# Sheet3.net
KiCad netlist of a schematic drawn in Altium Designer
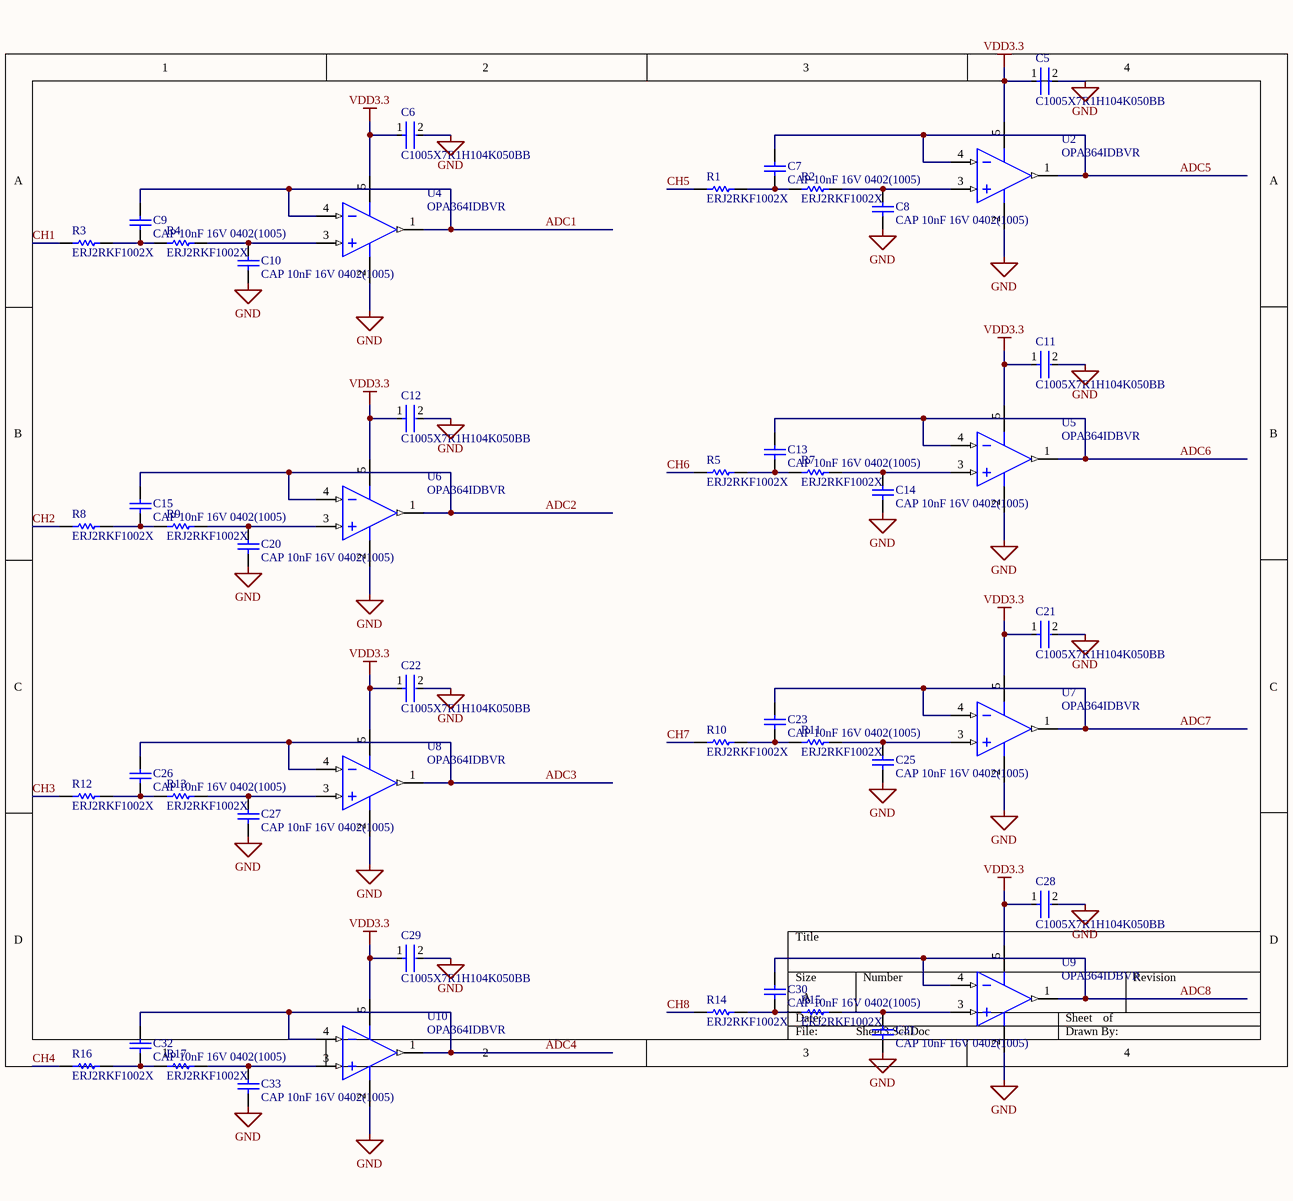
[diagram p0: Sheet3.SchDoc]

(export (version "E")
  (design (tool "Eeschema 10.0.6"))
  (components
    (comp (ref "C5")
      (value "C1005X7R1H104K050BB")
      (footprint "FP-C1005-050-0_05-IPC_C")
      (description "Multilayer Ceramic Capacitors 100nF ±10% 50V X7R SMD 0402")
      (fields (field (name "VOLTAGE") "50V") (field (name "TOLERANCE") "10%"))
      (libsource (lib "Altium Content Vault") (part "b4654b650e69147ec39a6b967a45e02"))
    )
    (comp (ref "C6")
      (value "C1005X7R1H104K050BB")
      (footprint "FP-C1005-050-0_05-IPC_C")
      (description "Multilayer Ceramic Capacitors 100nF ±10% 50V X7R SMD 0402")
      (fields (field (name "VOLTAGE") "50V") (field (name "TOLERANCE") "10%"))
      (libsource (lib "Altium Content Vault") (part "b4654b650e69147ec39a6b967a45e02"))
    )
    (comp (ref "C7")
      (value "CAP 10nF 16V 0402(1005)")
      (footprint "CAPC0402(1005)60_M")
      (description "CAP 10nF 16V -20% to +80% 0402 (1005 Metric) Thickness 0.6mm SMD")
      (fields (field (name "TOLERANCE") "-20% to +80%"))
      (libsource (lib "Altium Content Vault") (part "CAP"))
    )
    (comp (ref "C8")
      (value "CAP 10nF 16V 0402(1005)")
      (footprint "CAPC0402(1005)60_M")
      (description "CAP 10nF 16V -20% to +80% 0402 (1005 Metric) Thickness 0.6mm SMD")
      (fields (field (name "TOLERANCE") "-20% to +80%"))
      (libsource (lib "Altium Content Vault") (part "CAP"))
    )
    (comp (ref "C9")
      (value "CAP 10nF 16V 0402(1005)")
      (footprint "CAPC0402(1005)60_M")
      (description "CAP 10nF 16V -20% to +80% 0402 (1005 Metric) Thickness 0.6mm SMD")
      (fields (field (name "TOLERANCE") "-20% to +80%"))
      (libsource (lib "Altium Content Vault") (part "CAP"))
    )
    (comp (ref "C10")
      (value "CAP 10nF 16V 0402(1005)")
      (footprint "CAPC0402(1005)60_M")
      (description "CAP 10nF 16V -20% to +80% 0402 (1005 Metric) Thickness 0.6mm SMD")
      (fields (field (name "TOLERANCE") "-20% to +80%"))
      (libsource (lib "Altium Content Vault") (part "CAP"))
    )
    (comp (ref "C11")
      (value "C1005X7R1H104K050BB")
      (footprint "FP-C1005-050-0_05-IPC_C")
      (description "Multilayer Ceramic Capacitors 100nF ±10% 50V X7R SMD 0402")
      (fields (field (name "VOLTAGE") "50V") (field (name "TOLERANCE") "10%"))
      (libsource (lib "Altium Content Vault") (part "b4654b650e69147ec39a6b967a45e02"))
    )
    (comp (ref "C12")
      (value "C1005X7R1H104K050BB")
      (footprint "FP-C1005-050-0_05-IPC_C")
      (description "Multilayer Ceramic Capacitors 100nF ±10% 50V X7R SMD 0402")
      (fields (field (name "VOLTAGE") "50V") (field (name "TOLERANCE") "10%"))
      (libsource (lib "Altium Content Vault") (part "b4654b650e69147ec39a6b967a45e02"))
    )
    (comp (ref "C13")
      (value "CAP 10nF 16V 0402(1005)")
      (footprint "CAPC0402(1005)60_M")
      (description "CAP 10nF 16V -20% to +80% 0402 (1005 Metric) Thickness 0.6mm SMD")
      (fields (field (name "TOLERANCE") "-20% to +80%"))
      (libsource (lib "Altium Content Vault") (part "CAP"))
    )
    (comp (ref "C14")
      (value "CAP 10nF 16V 0402(1005)")
      (footprint "CAPC0402(1005)60_M")
      (description "CAP 10nF 16V -20% to +80% 0402 (1005 Metric) Thickness 0.6mm SMD")
      (fields (field (name "TOLERANCE") "-20% to +80%"))
      (libsource (lib "Altium Content Vault") (part "CAP"))
    )
    (comp (ref "C15")
      (value "CAP 10nF 16V 0402(1005)")
      (footprint "CAPC0402(1005)60_M")
      (description "CAP 10nF 16V -20% to +80% 0402 (1005 Metric) Thickness 0.6mm SMD")
      (fields (field (name "TOLERANCE") "-20% to +80%"))
      (libsource (lib "Altium Content Vault") (part "CAP"))
    )
    (comp (ref "C20")
      (value "CAP 10nF 16V 0402(1005)")
      (footprint "CAPC0402(1005)60_M")
      (description "CAP 10nF 16V -20% to +80% 0402 (1005 Metric) Thickness 0.6mm SMD")
      (fields (field (name "TOLERANCE") "-20% to +80%"))
      (libsource (lib "Altium Content Vault") (part "CAP"))
    )
    (comp (ref "C21")
      (value "C1005X7R1H104K050BB")
      (footprint "FP-C1005-050-0_05-IPC_C")
      (description "Multilayer Ceramic Capacitors 100nF ±10% 50V X7R SMD 0402")
      (fields (field (name "VOLTAGE") "50V") (field (name "TOLERANCE") "10%"))
      (libsource (lib "Altium Content Vault") (part "b4654b650e69147ec39a6b967a45e02"))
    )
    (comp (ref "C22")
      (value "C1005X7R1H104K050BB")
      (footprint "FP-C1005-050-0_05-IPC_C")
      (description "Multilayer Ceramic Capacitors 100nF ±10% 50V X7R SMD 0402")
      (fields (field (name "VOLTAGE") "50V") (field (name "TOLERANCE") "10%"))
      (libsource (lib "Altium Content Vault") (part "b4654b650e69147ec39a6b967a45e02"))
    )
    (comp (ref "C23")
      (value "CAP 10nF 16V 0402(1005)")
      (footprint "CAPC0402(1005)60_M")
      (description "CAP 10nF 16V -20% to +80% 0402 (1005 Metric) Thickness 0.6mm SMD")
      (fields (field (name "TOLERANCE") "-20% to +80%"))
      (libsource (lib "Altium Content Vault") (part "CAP"))
    )
    (comp (ref "C25")
      (value "CAP 10nF 16V 0402(1005)")
      (footprint "CAPC0402(1005)60_M")
      (description "CAP 10nF 16V -20% to +80% 0402 (1005 Metric) Thickness 0.6mm SMD")
      (fields (field (name "TOLERANCE") "-20% to +80%"))
      (libsource (lib "Altium Content Vault") (part "CAP"))
    )
    (comp (ref "C26")
      (value "CAP 10nF 16V 0402(1005)")
      (footprint "CAPC0402(1005)60_M")
      (description "CAP 10nF 16V -20% to +80% 0402 (1005 Metric) Thickness 0.6mm SMD")
      (fields (field (name "TOLERANCE") "-20% to +80%"))
      (libsource (lib "Altium Content Vault") (part "CAP"))
    )
    (comp (ref "C27")
      (value "CAP 10nF 16V 0402(1005)")
      (footprint "CAPC0402(1005)60_M")
      (description "CAP 10nF 16V -20% to +80% 0402 (1005 Metric) Thickness 0.6mm SMD")
      (fields (field (name "TOLERANCE") "-20% to +80%"))
      (libsource (lib "Altium Content Vault") (part "CAP"))
    )
    (comp (ref "C28")
      (value "C1005X7R1H104K050BB")
      (footprint "FP-C1005-050-0_05-IPC_C")
      (description "Multilayer Ceramic Capacitors 100nF ±10% 50V X7R SMD 0402")
      (fields (field (name "VOLTAGE") "50V") (field (name "TOLERANCE") "10%"))
      (libsource (lib "Altium Content Vault") (part "b4654b650e69147ec39a6b967a45e02"))
    )
    (comp (ref "C29")
      (value "C1005X7R1H104K050BB")
      (footprint "FP-C1005-050-0_05-IPC_C")
      (description "Multilayer Ceramic Capacitors 100nF ±10% 50V X7R SMD 0402")
      (fields (field (name "VOLTAGE") "50V") (field (name "TOLERANCE") "10%"))
      (libsource (lib "Altium Content Vault") (part "b4654b650e69147ec39a6b967a45e02"))
    )
    (comp (ref "C30")
      (value "CAP 10nF 16V 0402(1005)")
      (footprint "CAPC0402(1005)60_M")
      (description "CAP 10nF 16V -20% to +80% 0402 (1005 Metric) Thickness 0.6mm SMD")
      (fields (field (name "TOLERANCE") "-20% to +80%"))
      (libsource (lib "Altium Content Vault") (part "CAP"))
    )
    (comp (ref "C31")
      (value "CAP 10nF 16V 0402(1005)")
      (footprint "CAPC0402(1005)60_M")
      (description "CAP 10nF 16V -20% to +80% 0402 (1005 Metric) Thickness 0.6mm SMD")
      (fields (field (name "TOLERANCE") "-20% to +80%"))
      (libsource (lib "Altium Content Vault") (part "CAP"))
    )
    (comp (ref "C32")
      (value "CAP 10nF 16V 0402(1005)")
      (footprint "CAPC0402(1005)60_M")
      (description "CAP 10nF 16V -20% to +80% 0402 (1005 Metric) Thickness 0.6mm SMD")
      (fields (field (name "TOLERANCE") "-20% to +80%"))
      (libsource (lib "Altium Content Vault") (part "CAP"))
    )
    (comp (ref "C33")
      (value "CAP 10nF 16V 0402(1005)")
      (footprint "CAPC0402(1005)60_M")
      (description "CAP 10nF 16V -20% to +80% 0402 (1005 Metric) Thickness 0.6mm SMD")
      (fields (field (name "TOLERANCE") "-20% to +80%"))
      (libsource (lib "Altium Content Vault") (part "CAP"))
    )
    (comp (ref "R1")
      (value "ERJ2RKF1002X")
      (footprint "RESC1005X40X25LL05T05")
      (description "Chip Resistor, 10 KOhm, +/- 1%, 0.1 W, -55 to 155 degC, 0402 (1005 Metric), RoHS, Tape and Reel")
      (fields (field (name "TOLERANCE") "1%") (field (name "MANUFACTURER") "Panasonic"))
      (libsource (lib "Altium Content Vault") (part "RES-2"))
    )
    (comp (ref "R2")
      (value "ERJ2RKF1002X")
      (footprint "RESC1005X40X25LL05T05")
      (description "Chip Resistor, 10 KOhm, +/- 1%, 0.1 W, -55 to 155 degC, 0402 (1005 Metric), RoHS, Tape and Reel")
      (fields (field (name "TOLERANCE") "1%") (field (name "MANUFACTURER") "Panasonic"))
      (libsource (lib "Altium Content Vault") (part "RES-2"))
    )
    (comp (ref "R3")
      (value "ERJ2RKF1002X")
      (footprint "RESC1005X40X25LL05T05")
      (description "Chip Resistor, 10 KOhm, +/- 1%, 0.1 W, -55 to 155 degC, 0402 (1005 Metric), RoHS, Tape and Reel")
      (fields (field (name "TOLERANCE") "1%") (field (name "MANUFACTURER") "Panasonic"))
      (libsource (lib "Altium Content Vault") (part "RES-2"))
    )
    (comp (ref "R4")
      (value "ERJ2RKF1002X")
      (footprint "RESC1005X40X25LL05T05")
      (description "Chip Resistor, 10 KOhm, +/- 1%, 0.1 W, -55 to 155 degC, 0402 (1005 Metric), RoHS, Tape and Reel")
      (fields (field (name "TOLERANCE") "1%") (field (name "MANUFACTURER") "Panasonic"))
      (libsource (lib "Altium Content Vault") (part "RES-2"))
    )
    (comp (ref "R5")
      (value "ERJ2RKF1002X")
      (footprint "RESC1005X40X25LL05T05")
      (description "Chip Resistor, 10 KOhm, +/- 1%, 0.1 W, -55 to 155 degC, 0402 (1005 Metric), RoHS, Tape and Reel")
      (fields (field (name "TOLERANCE") "1%") (field (name "MANUFACTURER") "Panasonic"))
      (libsource (lib "Altium Content Vault") (part "RES-2"))
    )
    (comp (ref "R7")
      (value "ERJ2RKF1002X")
      (footprint "RESC1005X40X25LL05T05")
      (description "Chip Resistor, 10 KOhm, +/- 1%, 0.1 W, -55 to 155 degC, 0402 (1005 Metric), RoHS, Tape and Reel")
      (fields (field (name "TOLERANCE") "1%") (field (name "MANUFACTURER") "Panasonic"))
      (libsource (lib "Altium Content Vault") (part "RES-2"))
    )
    (comp (ref "R8")
      (value "ERJ2RKF1002X")
      (footprint "RESC1005X40X25LL05T05")
      (description "Chip Resistor, 10 KOhm, +/- 1%, 0.1 W, -55 to 155 degC, 0402 (1005 Metric), RoHS, Tape and Reel")
      (fields (field (name "TOLERANCE") "1%") (field (name "MANUFACTURER") "Panasonic"))
      (libsource (lib "Altium Content Vault") (part "RES-2"))
    )
    (comp (ref "R9")
      (value "ERJ2RKF1002X")
      (footprint "RESC1005X40X25LL05T05")
      (description "Chip Resistor, 10 KOhm, +/- 1%, 0.1 W, -55 to 155 degC, 0402 (1005 Metric), RoHS, Tape and Reel")
      (fields (field (name "TOLERANCE") "1%") (field (name "MANUFACTURER") "Panasonic"))
      (libsource (lib "Altium Content Vault") (part "RES-2"))
    )
    (comp (ref "R10")
      (value "ERJ2RKF1002X")
      (footprint "RESC1005X40X25LL05T05")
      (description "Chip Resistor, 10 KOhm, +/- 1%, 0.1 W, -55 to 155 degC, 0402 (1005 Metric), RoHS, Tape and Reel")
      (fields (field (name "TOLERANCE") "1%") (field (name "MANUFACTURER") "Panasonic"))
      (libsource (lib "Altium Content Vault") (part "RES-2"))
    )
    (comp (ref "R11")
      (value "ERJ2RKF1002X")
      (footprint "RESC1005X40X25LL05T05")
      (description "Chip Resistor, 10 KOhm, +/- 1%, 0.1 W, -55 to 155 degC, 0402 (1005 Metric), RoHS, Tape and Reel")
      (fields (field (name "TOLERANCE") "1%") (field (name "MANUFACTURER") "Panasonic"))
      (libsource (lib "Altium Content Vault") (part "RES-2"))
    )
    (comp (ref "R12")
      (value "ERJ2RKF1002X")
      (footprint "RESC1005X40X25LL05T05")
      (description "Chip Resistor, 10 KOhm, +/- 1%, 0.1 W, -55 to 155 degC, 0402 (1005 Metric), RoHS, Tape and Reel")
      (fields (field (name "TOLERANCE") "1%") (field (name "MANUFACTURER") "Panasonic"))
      (libsource (lib "Altium Content Vault") (part "RES-2"))
    )
    (comp (ref "R13")
      (value "ERJ2RKF1002X")
      (footprint "RESC1005X40X25LL05T05")
      (description "Chip Resistor, 10 KOhm, +/- 1%, 0.1 W, -55 to 155 degC, 0402 (1005 Metric), RoHS, Tape and Reel")
      (fields (field (name "TOLERANCE") "1%") (field (name "MANUFACTURER") "Panasonic"))
      (libsource (lib "Altium Content Vault") (part "RES-2"))
    )
    (comp (ref "R14")
      (value "ERJ2RKF1002X")
      (footprint "RESC1005X40X25LL05T05")
      (description "Chip Resistor, 10 KOhm, +/- 1%, 0.1 W, -55 to 155 degC, 0402 (1005 Metric), RoHS, Tape and Reel")
      (fields (field (name "TOLERANCE") "1%") (field (name "MANUFACTURER") "Panasonic"))
      (libsource (lib "Altium Content Vault") (part "RES-2"))
    )
    (comp (ref "R15")
      (value "ERJ2RKF1002X")
      (footprint "RESC1005X40X25LL05T05")
      (description "Chip Resistor, 10 KOhm, +/- 1%, 0.1 W, -55 to 155 degC, 0402 (1005 Metric), RoHS, Tape and Reel")
      (fields (field (name "TOLERANCE") "1%") (field (name "MANUFACTURER") "Panasonic"))
      (libsource (lib "Altium Content Vault") (part "RES-2"))
    )
    (comp (ref "R16")
      (value "ERJ2RKF1002X")
      (footprint "RESC1005X40X25LL05T05")
      (description "Chip Resistor, 10 KOhm, +/- 1%, 0.1 W, -55 to 155 degC, 0402 (1005 Metric), RoHS, Tape and Reel")
      (fields (field (name "TOLERANCE") "1%") (field (name "MANUFACTURER") "Panasonic"))
      (libsource (lib "Altium Content Vault") (part "RES-2"))
    )
    (comp (ref "R17")
      (value "ERJ2RKF1002X")
      (footprint "RESC1005X40X25LL05T05")
      (description "Chip Resistor, 10 KOhm, +/- 1%, 0.1 W, -55 to 155 degC, 0402 (1005 Metric), RoHS, Tape and Reel")
      (fields (field (name "TOLERANCE") "1%") (field (name "MANUFACTURER") "Panasonic"))
      (libsource (lib "Altium Content Vault") (part "RES-2"))
    )
    (comp (ref "U2")
      (value "OPA364IDBVR")
      (footprint "DBV0005A_M")
      (fields (field (name "MANUFACTURER") "Texas Instruments"))
      (libsource (lib "Altium Content Vault") (part "TI-OPA364_5DBV5"))
    )
    (comp (ref "U4")
      (value "OPA364IDBVR")
      (footprint "DBV0005A_M")
      (fields (field (name "MANUFACTURER") "Texas Instruments"))
      (libsource (lib "Altium Content Vault") (part "TI-OPA364_5DBV5"))
    )
    (comp (ref "U5")
      (value "OPA364IDBVR")
      (footprint "DBV0005A_M")
      (fields (field (name "MANUFACTURER") "Texas Instruments"))
      (libsource (lib "Altium Content Vault") (part "TI-OPA364_5DBV5"))
    )
    (comp (ref "U6")
      (value "OPA364IDBVR")
      (footprint "DBV0005A_M")
      (fields (field (name "MANUFACTURER") "Texas Instruments"))
      (libsource (lib "Altium Content Vault") (part "TI-OPA364_5DBV5"))
    )
    (comp (ref "U7")
      (value "OPA364IDBVR")
      (footprint "DBV0005A_M")
      (fields (field (name "MANUFACTURER") "Texas Instruments"))
      (libsource (lib "Altium Content Vault") (part "TI-OPA364_5DBV5"))
    )
    (comp (ref "U8")
      (value "OPA364IDBVR")
      (footprint "DBV0005A_M")
      (fields (field (name "MANUFACTURER") "Texas Instruments"))
      (libsource (lib "Altium Content Vault") (part "TI-OPA364_5DBV5"))
    )
    (comp (ref "U9")
      (value "OPA364IDBVR")
      (footprint "DBV0005A_M")
      (fields (field (name "MANUFACTURER") "Texas Instruments"))
      (libsource (lib "Altium Content Vault") (part "TI-OPA364_5DBV5"))
    )
    (comp (ref "U10")
      (value "OPA364IDBVR")
      (footprint "DBV0005A_M")
      (fields (field (name "MANUFACTURER") "Texas Instruments"))
      (libsource (lib "Altium Content Vault") (part "TI-OPA364_5DBV5"))
    )
  )
  (nets
    (net (code "1") (name "/ADC1") (class "Default")
      (node (ref "C9") (pin "2") (pinfunction "2_2") (pintype "passive"))
      (node (ref "U4") (pin "1") (pinfunction "VOUT_1") (pintype "output"))
      (node (ref "U4") (pin "4") (pinfunction "IN-_4") (pintype "input"))
    )
    (net (code "2") (name "/ADC2") (class "Default")
      (node (ref "C15") (pin "2") (pinfunction "2_2") (pintype "passive"))
      (node (ref "U6") (pin "1") (pinfunction "VOUT_1") (pintype "output"))
      (node (ref "U6") (pin "4") (pinfunction "IN-_4") (pintype "input"))
    )
    (net (code "3") (name "/ADC3") (class "Default")
      (node (ref "C26") (pin "2") (pinfunction "2_2") (pintype "passive"))
      (node (ref "U8") (pin "1") (pinfunction "VOUT_1") (pintype "output"))
      (node (ref "U8") (pin "4") (pinfunction "IN-_4") (pintype "input"))
    )
    (net (code "4") (name "/ADC4") (class "Default")
      (node (ref "C32") (pin "2") (pinfunction "2_2") (pintype "passive"))
      (node (ref "U10") (pin "1") (pinfunction "VOUT_1") (pintype "output"))
      (node (ref "U10") (pin "4") (pinfunction "IN-_4") (pintype "input"))
    )
    (net (code "5") (name "/ADC5") (class "Default")
      (node (ref "C7") (pin "2") (pinfunction "2_2") (pintype "passive"))
      (node (ref "U2") (pin "1") (pinfunction "VOUT_1") (pintype "output"))
      (node (ref "U2") (pin "4") (pinfunction "IN-_4") (pintype "input"))
    )
    (net (code "6") (name "/ADC6") (class "Default")
      (node (ref "C13") (pin "2") (pinfunction "2_2") (pintype "passive"))
      (node (ref "U5") (pin "1") (pinfunction "VOUT_1") (pintype "output"))
      (node (ref "U5") (pin "4") (pinfunction "IN-_4") (pintype "input"))
    )
    (net (code "7") (name "/ADC7") (class "Default")
      (node (ref "C23") (pin "2") (pinfunction "2_2") (pintype "passive"))
      (node (ref "U7") (pin "1") (pinfunction "VOUT_1") (pintype "output"))
      (node (ref "U7") (pin "4") (pinfunction "IN-_4") (pintype "input"))
    )
    (net (code "8") (name "/ADC8") (class "Default")
      (node (ref "C30") (pin "2") (pinfunction "2_2") (pintype "passive"))
      (node (ref "U9") (pin "1") (pinfunction "VOUT_1") (pintype "output"))
      (node (ref "U9") (pin "4") (pinfunction "IN-_4") (pintype "input"))
    )
    (net (code "9") (name "/CH1") (class "Default")
      (node (ref "R3") (pin "1") (pinfunction "1_1") (pintype "passive"))
    )
    (net (code "10") (name "/CH2") (class "Default")
      (node (ref "R8") (pin "1") (pinfunction "1_1") (pintype "passive"))
    )
    (net (code "11") (name "/CH3") (class "Default")
      (node (ref "R12") (pin "1") (pinfunction "1_1") (pintype "passive"))
    )
    (net (code "12") (name "/CH4") (class "Default")
      (node (ref "R16") (pin "1") (pinfunction "1_1") (pintype "passive"))
    )
    (net (code "13") (name "/CH5") (class "Default")
      (node (ref "R1") (pin "1") (pinfunction "1_1") (pintype "passive"))
    )
    (net (code "14") (name "/CH6") (class "Default")
      (node (ref "R5") (pin "1") (pinfunction "1_1") (pintype "passive"))
    )
    (net (code "15") (name "/CH7") (class "Default")
      (node (ref "R10") (pin "1") (pinfunction "1_1") (pintype "passive"))
    )
    (net (code "16") (name "/CH8") (class "Default")
      (node (ref "R14") (pin "1") (pinfunction "1_1") (pintype "passive"))
    )
    (net (code "17") (name "GND") (class "Default")
      (node (ref "C10") (pin "1") (pinfunction "1_1") (pintype "passive"))
      (node (ref "C11") (pin "2") (pinfunction "2_2") (pintype "passive"))
      (node (ref "C12") (pin "2") (pinfunction "2_2") (pintype "passive"))
      (node (ref "C14") (pin "1") (pinfunction "1_1") (pintype "passive"))
      (node (ref "C20") (pin "1") (pinfunction "1_1") (pintype "passive"))
      (node (ref "C21") (pin "2") (pinfunction "2_2") (pintype "passive"))
      (node (ref "C22") (pin "2") (pinfunction "2_2") (pintype "passive"))
      (node (ref "C25") (pin "1") (pinfunction "1_1") (pintype "passive"))
      (node (ref "C27") (pin "1") (pinfunction "1_1") (pintype "passive"))
      (node (ref "C28") (pin "2") (pinfunction "2_2") (pintype "passive"))
      (node (ref "C29") (pin "2") (pinfunction "2_2") (pintype "passive"))
      (node (ref "C31") (pin "1") (pinfunction "1_1") (pintype "passive"))
      (node (ref "C33") (pin "1") (pinfunction "1_1") (pintype "passive"))
      (node (ref "C5") (pin "2") (pinfunction "2_2") (pintype "passive"))
      (node (ref "C6") (pin "2") (pinfunction "2_2") (pintype "passive"))
      (node (ref "C8") (pin "1") (pinfunction "1_1") (pintype "passive"))
      (node (ref "U10") (pin "2") (pinfunction "V-_2") (pintype "power_in"))
      (node (ref "U2") (pin "2") (pinfunction "V-_2") (pintype "power_in"))
      (node (ref "U4") (pin "2") (pinfunction "V-_2") (pintype "power_in"))
      (node (ref "U5") (pin "2") (pinfunction "V-_2") (pintype "power_in"))
      (node (ref "U6") (pin "2") (pinfunction "V-_2") (pintype "power_in"))
      (node (ref "U7") (pin "2") (pinfunction "V-_2") (pintype "power_in"))
      (node (ref "U8") (pin "2") (pinfunction "V-_2") (pintype "power_in"))
      (node (ref "U9") (pin "2") (pinfunction "V-_2") (pintype "power_in"))
    )
    (net (code "18") (name "Net-(C7-Pad1)") (class "Default")
      (node (ref "C7") (pin "1") (pinfunction "1_1") (pintype "passive"))
      (node (ref "R1") (pin "2") (pinfunction "2_2") (pintype "passive"))
      (node (ref "R2") (pin "1") (pinfunction "1_1") (pintype "passive"))
    )
    (net (code "19") (name "Net-(C9-Pad1)") (class "Default")
      (node (ref "C9") (pin "1") (pinfunction "1_1") (pintype "passive"))
      (node (ref "R3") (pin "2") (pinfunction "2_2") (pintype "passive"))
      (node (ref "R4") (pin "1") (pinfunction "1_1") (pintype "passive"))
    )
    (net (code "20") (name "Net-(C13-Pad1)") (class "Default")
      (node (ref "C13") (pin "1") (pinfunction "1_1") (pintype "passive"))
      (node (ref "R5") (pin "2") (pinfunction "2_2") (pintype "passive"))
      (node (ref "R7") (pin "1") (pinfunction "1_1") (pintype "passive"))
    )
    (net (code "21") (name "Net-(C15-Pad1)") (class "Default")
      (node (ref "C15") (pin "1") (pinfunction "1_1") (pintype "passive"))
      (node (ref "R8") (pin "2") (pinfunction "2_2") (pintype "passive"))
      (node (ref "R9") (pin "1") (pinfunction "1_1") (pintype "passive"))
    )
    (net (code "22") (name "Net-(C23-Pad1)") (class "Default")
      (node (ref "C23") (pin "1") (pinfunction "1_1") (pintype "passive"))
      (node (ref "R10") (pin "2") (pinfunction "2_2") (pintype "passive"))
      (node (ref "R11") (pin "1") (pinfunction "1_1") (pintype "passive"))
    )
    (net (code "23") (name "Net-(C26-Pad1)") (class "Default")
      (node (ref "C26") (pin "1") (pinfunction "1_1") (pintype "passive"))
      (node (ref "R12") (pin "2") (pinfunction "2_2") (pintype "passive"))
      (node (ref "R13") (pin "1") (pinfunction "1_1") (pintype "passive"))
    )
    (net (code "24") (name "Net-(C30-Pad1)") (class "Default")
      (node (ref "C30") (pin "1") (pinfunction "1_1") (pintype "passive"))
      (node (ref "R14") (pin "2") (pinfunction "2_2") (pintype "passive"))
      (node (ref "R15") (pin "1") (pinfunction "1_1") (pintype "passive"))
    )
    (net (code "25") (name "Net-(C32-Pad1)") (class "Default")
      (node (ref "C32") (pin "1") (pinfunction "1_1") (pintype "passive"))
      (node (ref "R16") (pin "2") (pinfunction "2_2") (pintype "passive"))
      (node (ref "R17") (pin "1") (pinfunction "1_1") (pintype "passive"))
    )
    (net (code "26") (name "Net-(U2-IN+)") (class "Default")
      (node (ref "C8") (pin "2") (pinfunction "2_2") (pintype "passive"))
      (node (ref "R2") (pin "2") (pinfunction "2_2") (pintype "passive"))
      (node (ref "U2") (pin "3") (pinfunction "IN+_3") (pintype "input"))
    )
    (net (code "27") (name "Net-(U4-IN+)") (class "Default")
      (node (ref "C10") (pin "2") (pinfunction "2_2") (pintype "passive"))
      (node (ref "R4") (pin "2") (pinfunction "2_2") (pintype "passive"))
      (node (ref "U4") (pin "3") (pinfunction "IN+_3") (pintype "input"))
    )
    (net (code "28") (name "Net-(U5-IN+)") (class "Default")
      (node (ref "C14") (pin "2") (pinfunction "2_2") (pintype "passive"))
      (node (ref "R7") (pin "2") (pinfunction "2_2") (pintype "passive"))
      (node (ref "U5") (pin "3") (pinfunction "IN+_3") (pintype "input"))
    )
    (net (code "29") (name "Net-(U6-IN+)") (class "Default")
      (node (ref "C20") (pin "2") (pinfunction "2_2") (pintype "passive"))
      (node (ref "R9") (pin "2") (pinfunction "2_2") (pintype "passive"))
      (node (ref "U6") (pin "3") (pinfunction "IN+_3") (pintype "input"))
    )
    (net (code "30") (name "Net-(U7-IN+)") (class "Default")
      (node (ref "C25") (pin "2") (pinfunction "2_2") (pintype "passive"))
      (node (ref "R11") (pin "2") (pinfunction "2_2") (pintype "passive"))
      (node (ref "U7") (pin "3") (pinfunction "IN+_3") (pintype "input"))
    )
    (net (code "31") (name "Net-(U8-IN+)") (class "Default")
      (node (ref "C27") (pin "2") (pinfunction "2_2") (pintype "passive"))
      (node (ref "R13") (pin "2") (pinfunction "2_2") (pintype "passive"))
      (node (ref "U8") (pin "3") (pinfunction "IN+_3") (pintype "input"))
    )
    (net (code "32") (name "Net-(U9-IN+)") (class "Default")
      (node (ref "C31") (pin "2") (pinfunction "2_2") (pintype "passive"))
      (node (ref "R15") (pin "2") (pinfunction "2_2") (pintype "passive"))
      (node (ref "U9") (pin "3") (pinfunction "IN+_3") (pintype "input"))
    )
    (net (code "33") (name "Net-(U10-IN+)") (class "Default")
      (node (ref "C33") (pin "2") (pinfunction "2_2") (pintype "passive"))
      (node (ref "R17") (pin "2") (pinfunction "2_2") (pintype "passive"))
      (node (ref "U10") (pin "3") (pinfunction "IN+_3") (pintype "input"))
    )
    (net (code "34") (name "VDD3.3") (class "Default")
      (node (ref "C11") (pin "1") (pinfunction "1_1") (pintype "passive"))
      (node (ref "C12") (pin "1") (pinfunction "1_1") (pintype "passive"))
      (node (ref "C21") (pin "1") (pinfunction "1_1") (pintype "passive"))
      (node (ref "C22") (pin "1") (pinfunction "1_1") (pintype "passive"))
      (node (ref "C28") (pin "1") (pinfunction "1_1") (pintype "passive"))
      (node (ref "C29") (pin "1") (pinfunction "1_1") (pintype "passive"))
      (node (ref "C5") (pin "1") (pinfunction "1_1") (pintype "passive"))
      (node (ref "C6") (pin "1") (pinfunction "1_1") (pintype "passive"))
      (node (ref "U10") (pin "5") (pinfunction "V+_5") (pintype "power_in"))
      (node (ref "U2") (pin "5") (pinfunction "V+_5") (pintype "power_in"))
      (node (ref "U4") (pin "5") (pinfunction "V+_5") (pintype "power_in"))
      (node (ref "U5") (pin "5") (pinfunction "V+_5") (pintype "power_in"))
      (node (ref "U6") (pin "5") (pinfunction "V+_5") (pintype "power_in"))
      (node (ref "U7") (pin "5") (pinfunction "V+_5") (pintype "power_in"))
      (node (ref "U8") (pin "5") (pinfunction "V+_5") (pintype "power_in"))
      (node (ref "U9") (pin "5") (pinfunction "V+_5") (pintype "power_in"))
    )
  )
)
